# SourceFollower_TSFP-4-1_Simple.net
KiCad netlist of a schematic drawn in Altium Designer
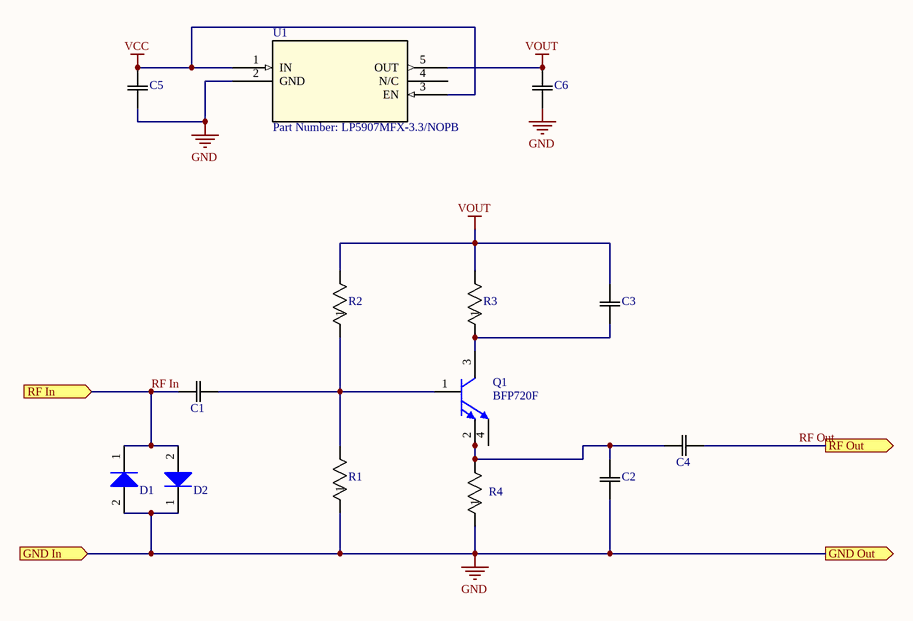
[diagram p0: SourceFollower_TSFP-4-1_Simple.SchDoc]

(export (version "E")
  (design (tool "Eeschema 10.0.6"))
  (components
    (comp (ref "C1")
      (value "Part Number: C0201C270J3GACTU")
      (footprint "C0201")
      (description "No Description Available")
      (fields
        (field (name "MANUFACTURER_PART_NUMBER") "C0201C270J3GACTU")
        (field (name "COPYRIGHT") "Copyright (C) 2018 Accelerated Designs. All rights reserved")
      )
      (libsource (lib "0201Capacitor_Yageo") (part "C0201C270J3GACTU"))
    )
    (comp (ref "C2")
      (value "Part Number: C0201C270J3GACTU")
      (footprint "C0201")
      (description "No Description Available")
      (fields
        (field (name "MANUFACTURER_PART_NUMBER") "C0201C270J3GACTU")
        (field (name "COPYRIGHT") "Copyright (C) 2018 Accelerated Designs. All rights reserved")
      )
      (libsource (lib "0201Capacitor_Yageo") (part "C0201C270J3GACTU"))
    )
    (comp (ref "C3")
      (value "Part Number: C0201C270J3GACTU")
      (footprint "C0201")
      (description "No Description Available")
      (fields
        (field (name "MANUFACTURER_PART_NUMBER") "C0201C270J3GACTU")
        (field (name "COPYRIGHT") "Copyright (C) 2018 Accelerated Designs. All rights reserved")
      )
      (libsource (lib "0201Capacitor_Yageo") (part "C0201C270J3GACTU"))
    )
    (comp (ref "C4")
      (value "Part Number: C0201C270J3GACTU")
      (footprint "C0201")
      (description "No Description Available")
      (fields
        (field (name "MANUFACTURER_PART_NUMBER") "C0201C270J3GACTU")
        (field (name "COPYRIGHT") "Copyright (C) 2018 Accelerated Designs. All rights reserved")
      )
      (libsource (lib "0201Capacitor_Yageo") (part "C0201C270J3GACTU"))
    )
    (comp (ref "C5")
      (value "Part Number: CC0402KRX7R6BB104")
      (footprint "YAG_CC0402")
      (description "No Description Available")
      (fields
        (field (name "MANUFACTURER_PART_NUMBER") "CC0402KRX7R6BB104")
        (field (name "COPYRIGHT") "Copyright (C) 2018 Accelerated Designs. All rights reserved")
      )
      (libsource (lib "0402Capacitor_Yageo") (part "CC0402KRX7R6BB10"))
    )
    (comp (ref "C6")
      (value "Part Number: CC0402KRX7R6BB104")
      (footprint "YAG_CC0402")
      (description "No Description Available")
      (fields
        (field (name "MANUFACTURER_PART_NUMBER") "CC0402KRX7R6BB104")
        (field (name "COPYRIGHT") "Copyright (C) 2018 Accelerated Designs. All rights reserved")
      )
      (libsource (lib "0402Capacitor_Yageo") (part "CC0402KRX7R6BB10"))
    )
    (comp (ref "D1")
      (value "BAT15-03W")
      (footprint "INF-SOD323_V")
      (description "Single Silicon Schottky Diode, 110 mA IF Max, SOD32, Green")
      (fields (field (name "MANUFACTURER") "Infineon"))
      (libsource (lib "Infineon_RFSchottkyDiode_SOD323") (part "BAT15-03W"))
    )
    (comp (ref "D2")
      (value "BAT15-03W")
      (footprint "INF-SOD323_V")
      (description "Single Silicon Schottky Diode, 110 mA IF Max, SOD32, Green")
      (fields (field (name "MANUFACTURER") "Infineon"))
      (libsource (lib "Infineon_RFSchottkyDiode_SOD323") (part "BAT15-03W"))
    )
    (comp (ref "Q1")
      (value "BFP720F")
      (footprint "INF-TSFP-4-1_V")
      (fields (field (name "MANUFACTURER") "Infineon"))
      (libsource (lib "Infineon_RFBJT_TSFP-4-1") (part "BFP720F"))
    )
    (comp (ref "R1")
      (value "Part Number: RC0201FR-0718KL")
      (footprint "RES_RC0201_P6XP3")
      (description "No Description Available")
      (fields
        (field (name "MANUFACTURER_PART_NUMBER") "RC0201FR-0718KL")
        (field (name "COPYRIGHT") "Copyright (C) 2018 Accelerated Designs. All rights reserved")
      )
      (libsource (lib "0201Resistor_Yageo") (part "RC0201FR-0718KL"))
    )
    (comp (ref "R2")
      (value "Part Number: RC0201FR-0718KL")
      (footprint "RES_RC0201_P6XP3")
      (description "No Description Available")
      (fields
        (field (name "MANUFACTURER_PART_NUMBER") "RC0201FR-0718KL")
        (field (name "COPYRIGHT") "Copyright (C) 2018 Accelerated Designs. All rights reserved")
      )
      (libsource (lib "0201Resistor_Yageo") (part "RC0201FR-0718KL"))
    )
    (comp (ref "R3")
      (value "Part Number: RC0201FR-0718KL")
      (footprint "RES_RC0201_P6XP3")
      (description "No Description Available")
      (fields
        (field (name "MANUFACTURER_PART_NUMBER") "RC0201FR-0718KL")
        (field (name "COPYRIGHT") "Copyright (C) 2018 Accelerated Designs. All rights reserved")
      )
      (libsource (lib "0201Resistor_Yageo") (part "RC0201FR-0718KL"))
    )
    (comp (ref "R4")
      (value "Part Number: RC0201FR-0718KL")
      (footprint "RES_RC0201_P6XP3")
      (description "No Description Available")
      (fields
        (field (name "MANUFACTURER_PART_NUMBER") "RC0201FR-0718KL")
        (field (name "COPYRIGHT") "Copyright (C) 2018 Accelerated Designs. All rights reserved")
      )
      (libsource (lib "0201Resistor_Yageo") (part "RC0201FR-0718KL"))
    )
    (comp (ref "U1")
      (value "Part Number: LP5907MFX-3.3/NOPB")
      (footprint "DBV5")
      (description "No Description Available")
      (fields
        (field (name "MANUFACTURER_PART_NUMBER") "LP5907MFX-3.3/NOPB")
        (field (name "COPYRIGHT") "Copyright (C) 2018 Accelerated Designs. All rights reserved")
      )
      (libsource (lib "TI_LDO_3V3_SOT325") (part "LP5907MFX-3.3/NO"))
    )
  )
  (nets
    (net (code "1") (name "/RF In") (class "Default")
      (node (ref "C1") (pin "1") (pinfunction "1_1") (pintype "passive"))
      (node (ref "D1") (pin "1") (pinfunction "K_1") (pintype "passive"))
      (node (ref "D2") (pin "2") (pinfunction "A_2") (pintype "passive"))
    )
    (net (code "2") (name "/RF Out") (class "Default")
      (node (ref "C4") (pin "1") (pinfunction "1_1") (pintype "passive"))
    )
    (net (code "3") (name "GND") (class "Default")
      (node (ref "C2") (pin "1") (pinfunction "1_1") (pintype "passive"))
      (node (ref "C5") (pin "1") (pinfunction "1_1") (pintype "passive"))
      (node (ref "C6") (pin "1") (pinfunction "1_1") (pintype "passive"))
      (node (ref "D1") (pin "2") (pinfunction "A_2") (pintype "passive"))
      (node (ref "D2") (pin "1") (pinfunction "K_1") (pintype "passive"))
      (node (ref "R1") (pin "1") (pinfunction "1_1") (pintype "passive"))
      (node (ref "R4") (pin "1") (pinfunction "1_1") (pintype "passive"))
      (node (ref "U1") (pin "2") (pinfunction "GND_2") (pintype "power_in"))
    )
    (net (code "4") (name "Net-(C2-Pad2)") (class "Default")
      (node (ref "C2") (pin "2") (pinfunction "2_2") (pintype "passive"))
      (node (ref "C4") (pin "2") (pinfunction "2_2") (pintype "passive"))
      (node (ref "Q1") (pin "2") (pinfunction "E_2") (pintype "passive"))
      (node (ref "R4") (pin "2") (pinfunction "2_2") (pintype "passive"))
    )
    (net (code "5") (name "Net-(Q1-B)") (class "Default")
      (node (ref "C1") (pin "2") (pinfunction "2_2") (pintype "passive"))
      (node (ref "Q1") (pin "1") (pinfunction "B_1") (pintype "passive"))
      (node (ref "R1") (pin "2") (pinfunction "2_2") (pintype "passive"))
      (node (ref "R2") (pin "1") (pinfunction "1_1") (pintype "passive"))
    )
    (net (code "6") (name "Net-(Q1-C)") (class "Default")
      (node (ref "C3") (pin "1") (pinfunction "1_1") (pintype "passive"))
      (node (ref "Q1") (pin "3") (pinfunction "C_3") (pintype "passive"))
      (node (ref "R3") (pin "1") (pinfunction "1_1") (pintype "passive"))
    )
    (net (code "7") (name "VCC") (class "Default")
      (node (ref "C5") (pin "2") (pinfunction "2_2") (pintype "passive"))
      (node (ref "U1") (pin "1") (pinfunction "IN_1") (pintype "input"))
      (node (ref "U1") (pin "3") (pinfunction "EN_3") (pintype "input"))
    )
    (net (code "8") (name "VOUT") (class "Default")
      (node (ref "C3") (pin "2") (pinfunction "2_2") (pintype "passive"))
      (node (ref "C6") (pin "2") (pinfunction "2_2") (pintype "passive"))
      (node (ref "R2") (pin "2") (pinfunction "2_2") (pintype "passive"))
      (node (ref "R3") (pin "2") (pinfunction "2_2") (pintype "passive"))
      (node (ref "U1") (pin "5") (pinfunction "OUT_5") (pintype "output"))
    )
    (net (code "9") (name "unconnected-(Q1-E-Pad4)") (class "Default")
      (node (ref "Q1") (pin "4") (pinfunction "E_4") (pintype "passive"))
    )
    (net (code "10") (name "unconnected-(U1-N{slash}C-Pad4)") (class "Default")
      (node (ref "U1") (pin "4") (pinfunction "N/C_4") (pintype "passive"))
    )
  )
)
